# main_board.net
KiCad netlist of a schematic drawn in EAGLE
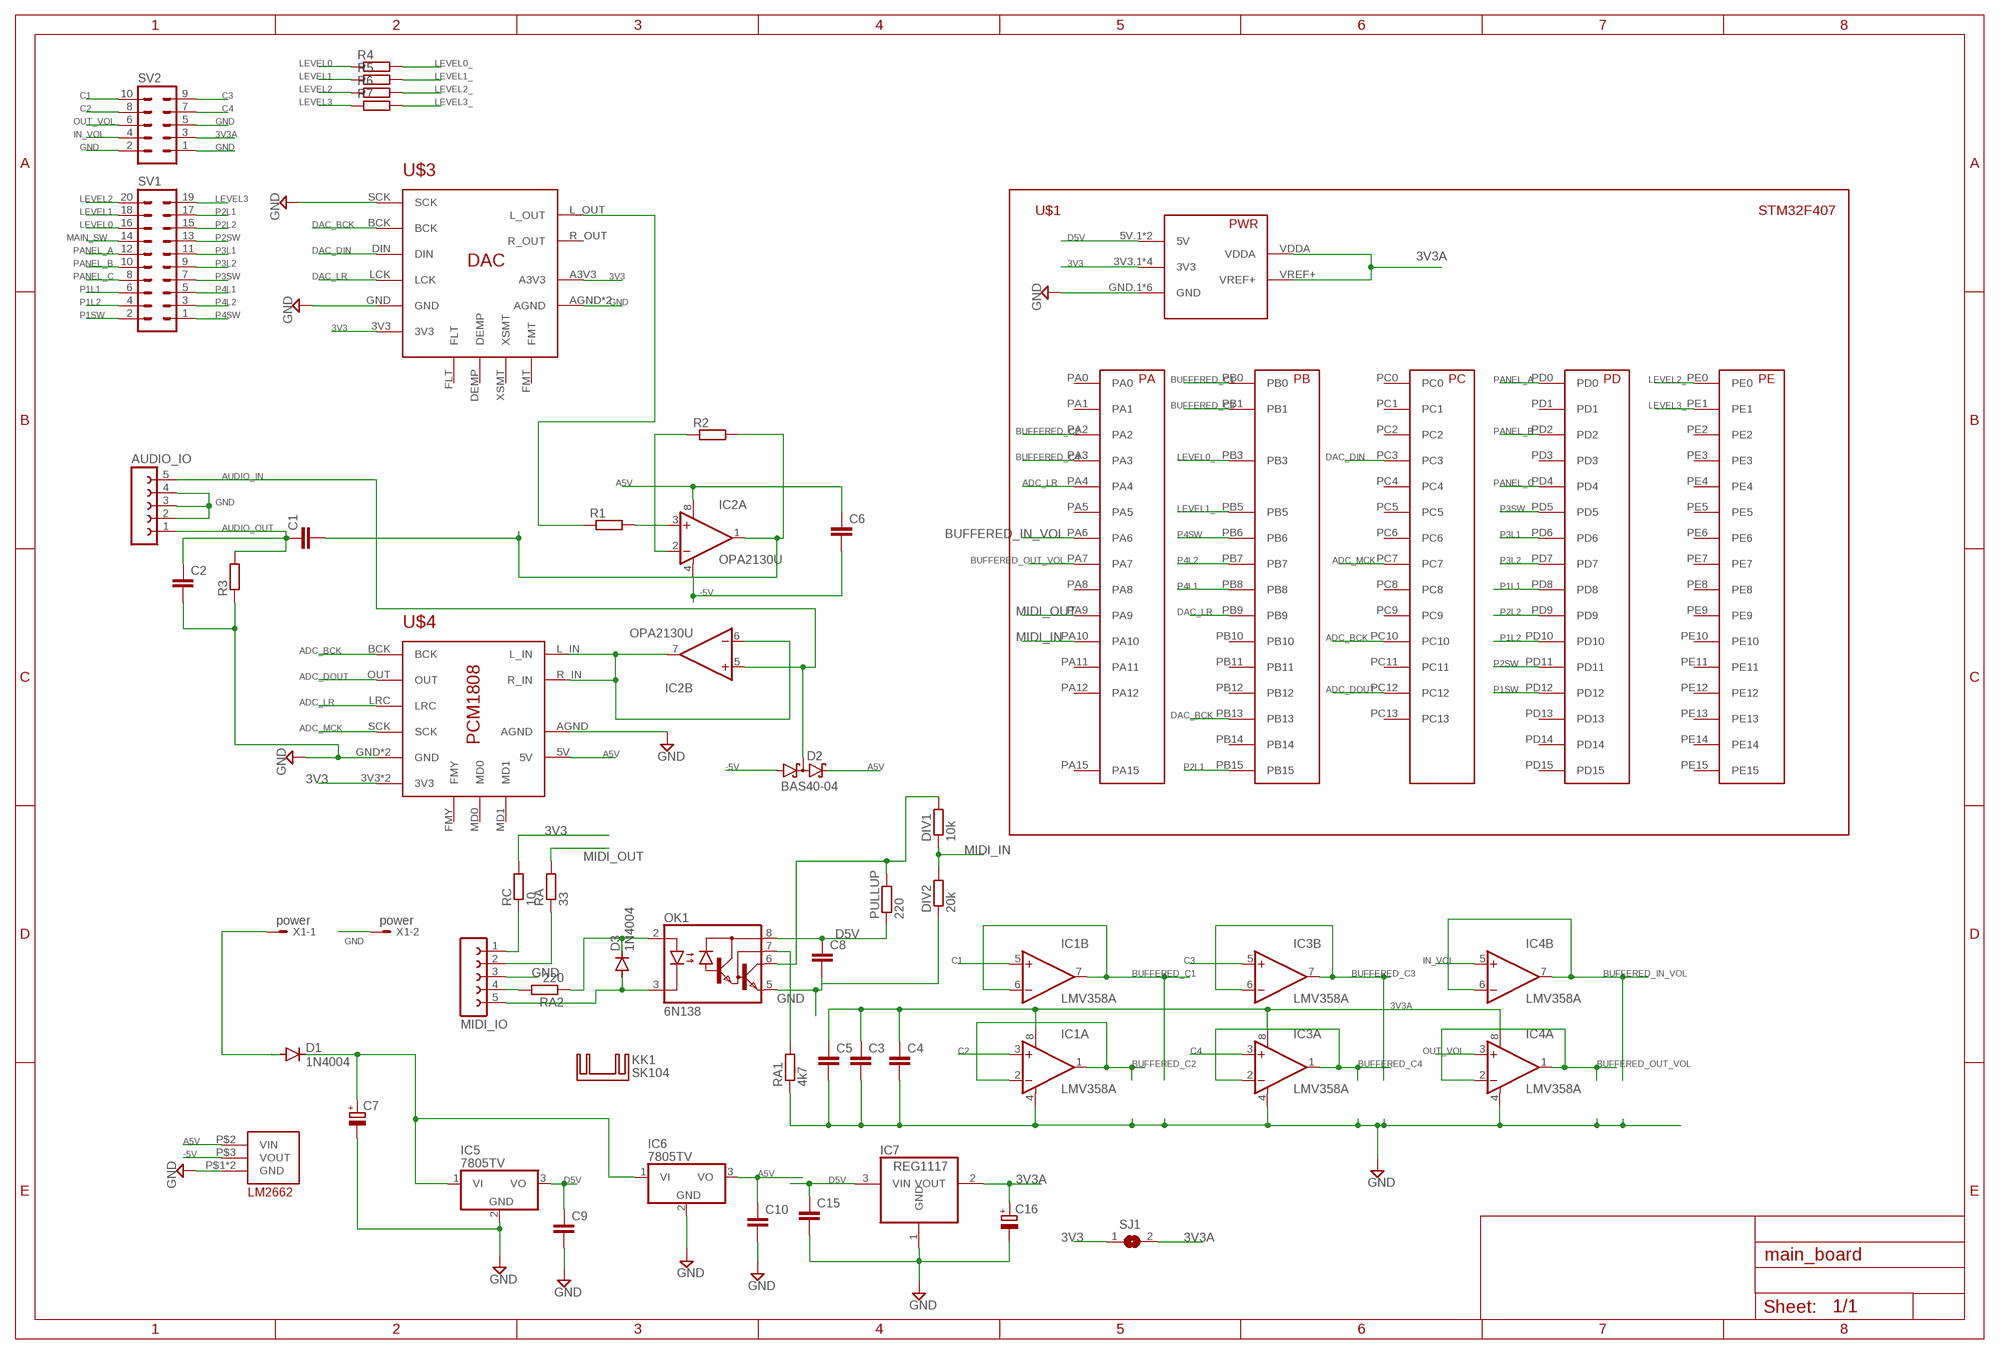
[diagram p0: schematic, sheet 1]

(export (version "E")
  (design (tool "Eeschema 10.0.6"))
  (components
    (comp (ref "AUDIO_IO")
      (value "FE05-1")
      (footprint "eagle-import:FE05-1")
      (libsource (lib "eagle-import") (part "FE05-1"))
    )
    (comp (ref "C1")
      (value "C5/5.5")
      (footprint "eagle-import:C5B5.5")
      (libsource (lib "eagle-import") (part "C5/5.5"))
    )
    (comp (ref "C2")
      (value "C2,5-3")
      (footprint "eagle-import:C2.5-3")
      (libsource (lib "eagle-import") (part "C2,5-3"))
    )
    (comp (ref "C3")
      (value "C-EUC0402")
      (footprint "eagle-import:C0402")
      (libsource (lib "eagle-import") (part "C-EUC0402"))
    )
    (comp (ref "C4")
      (value "C-EUC0402")
      (footprint "eagle-import:C0402")
      (libsource (lib "eagle-import") (part "C-EUC0402"))
    )
    (comp (ref "C5")
      (value "C-EUC0402")
      (footprint "eagle-import:C0402")
      (libsource (lib "eagle-import") (part "C-EUC0402"))
    )
    (comp (ref "C6")
      (value "C-EUC0402")
      (footprint "eagle-import:C0402")
      (libsource (lib "eagle-import") (part "C-EUC0402"))
    )
    (comp (ref "C7")
      (value "CPOL-EUE2.5-7")
      (footprint "eagle-import:E2,5-7")
      (libsource (lib "eagle-import") (part "CPOL-EUE2.5-7"))
    )
    (comp (ref "C8")
      (value "C-EU025-024X044")
      (footprint "eagle-import:C025-024X044")
      (libsource (lib "eagle-import") (part "C-EU025-024X044"))
    )
    (comp (ref "C9")
      (value "C-EU025-024X044")
      (footprint "eagle-import:C025-024X044")
      (libsource (lib "eagle-import") (part "C-EU025-024X044"))
    )
    (comp (ref "C10")
      (value "C-EU025-024X044")
      (footprint "eagle-import:C025-024X044")
      (libsource (lib "eagle-import") (part "C-EU025-024X044"))
    )
    (comp (ref "C15")
      (value "C-EUC0402")
      (footprint "eagle-import:C0402")
      (libsource (lib "eagle-import") (part "C-EUC0402"))
    )
    (comp (ref "C16")
      (value "CPOL-EUTT2D6L")
      (footprint "eagle-import:TT2D6L")
      (libsource (lib "eagle-import") (part "CPOL-EUTT2D6L"))
    )
    (comp (ref "D1")
      (value "1N4004")
      (footprint "eagle-import:DO41-10")
      (libsource (lib "eagle-import") (part "1N4004"))
    )
    (comp (ref "D2")
      (value "BAS40-04")
      (footprint "eagle-import:SOT23")
      (libsource (lib "eagle-import") (part "BAS40-04"))
    )
    (comp (ref "D3")
      (value "1N4004")
      (footprint "eagle-import:DO41-10")
      (libsource (lib "eagle-import") (part "1N4004"))
    )
    (comp (ref "DIV1")
      (value "10k")
      (footprint "eagle-import:0204V")
      (libsource (lib "eagle-import") (part "R-EU_0204/2V"))
    )
    (comp (ref "DIV2")
      (value "20k")
      (footprint "eagle-import:0204V")
      (libsource (lib "eagle-import") (part "R-EU_0204/2V"))
    )
    (comp (ref "IC1")
      (value "LMV358A")
      (footprint "eagle-import:SO08")
      (fields (field (name "MF") "TEXAS INSTRUMENTS") (field (name "MPN") "OPA2130UA"))
      (libsource (lib "eagle-import") (part "OPA2130U"))
    )
    (comp (ref "IC2")
      (value "OPA2130U")
      (footprint "eagle-import:SO08")
      (fields (field (name "MF") "TEXAS INSTRUMENTS") (field (name "MPN") "OPA2130UA"))
      (libsource (lib "eagle-import") (part "OPA2130U"))
    )
    (comp (ref "IC3")
      (value "LMV358A")
      (footprint "eagle-import:SO08")
      (fields (field (name "MF") "TEXAS INSTRUMENTS") (field (name "MPN") "OPA2130UA"))
      (libsource (lib "eagle-import") (part "OPA2130U"))
    )
    (comp (ref "IC4")
      (value "LMV358A")
      (footprint "eagle-import:SO08")
      (fields (field (name "MF") "TEXAS INSTRUMENTS") (field (name "MPN") "OPA2130UA"))
      (libsource (lib "eagle-import") (part "OPA2130U"))
    )
    (comp (ref "IC5")
      (value "7805TV")
      (footprint "eagle-import:TO220V")
      (libsource (lib "eagle-import") (part "78TV05"))
    )
    (comp (ref "IC6")
      (value "7805TV")
      (footprint "eagle-import:TO220V")
      (libsource (lib "eagle-import") (part "78TV05"))
    )
    (comp (ref "IC7")
      (value "REG1117")
      (footprint "eagle-import:SOT223")
      (libsource (lib "eagle-import") (part "REG1117"))
    )
    (comp (ref "KK1")
      (value "SK104")
      (footprint "eagle-import:SK104")
      (libsource (lib "eagle-import") (part "SK104"))
    )
    (comp (ref "MIDI_IO")
      (value "FE05-1")
      (footprint "eagle-import:FE05-1")
      (libsource (lib "eagle-import") (part "FE05-1"))
    )
    (comp (ref "OK1")
      (value "6N138")
      (footprint "eagle-import:DIL08")
      (fields (field (name "MF") "VISHAY/TELEFUNKEN"))
      (libsource (lib "eagle-import") (part "6N138"))
    )
    (comp (ref "PULLUP")
      (value "220")
      (footprint "eagle-import:0204V")
      (libsource (lib "eagle-import") (part "R-EU_0204/2V"))
    )
    (comp (ref "R1")
      (value "R-EU_0204/2V")
      (footprint "eagle-import:0204V")
      (libsource (lib "eagle-import") (part "R-EU_0204/2V"))
    )
    (comp (ref "R2")
      (value "R-EU_0204/2V")
      (footprint "eagle-import:0204V")
      (libsource (lib "eagle-import") (part "R-EU_0204/2V"))
    )
    (comp (ref "R3")
      (value "R-EU_0204/2V")
      (footprint "eagle-import:0204V")
      (libsource (lib "eagle-import") (part "R-EU_0204/2V"))
    )
    (comp (ref "R4")
      (value "R-EU_R0402")
      (footprint "eagle-import:R0402")
      (libsource (lib "eagle-import") (part "R-EU_R0402"))
    )
    (comp (ref "R5")
      (value "R-EU_R0402")
      (footprint "eagle-import:R0402")
      (libsource (lib "eagle-import") (part "R-EU_R0402"))
    )
    (comp (ref "R6")
      (value "R-EU_R0402")
      (footprint "eagle-import:R0402")
      (libsource (lib "eagle-import") (part "R-EU_R0402"))
    )
    (comp (ref "R7")
      (value "R-EU_R0402")
      (footprint "eagle-import:R0402")
      (libsource (lib "eagle-import") (part "R-EU_R0402"))
    )
    (comp (ref "RA")
      (value "33")
      (footprint "eagle-import:0204V")
      (libsource (lib "eagle-import") (part "R-EU_0204/2V"))
    )
    (comp (ref "RA1")
      (value "4k7")
      (footprint "eagle-import:0204V")
      (libsource (lib "eagle-import") (part "R-EU_0204/2V"))
    )
    (comp (ref "RA2")
      (value "220")
      (footprint "eagle-import:0204V")
      (libsource (lib "eagle-import") (part "R-EU_0204/2V"))
    )
    (comp (ref "RC")
      (value "10")
      (footprint "eagle-import:0204V")
      (libsource (lib "eagle-import") (part "R-EU_0204/2V"))
    )
    (comp (ref "SJ1") (value "SJ") (footprint "eagle-import:SJ") (libsource (lib "eagle-import") (part "SJ")))
    (comp (ref "SV1")
      (value "MA10-2")
      (footprint "eagle-import:MA10-2")
      (libsource (lib "eagle-import") (part "MA10-2"))
    )
    (comp (ref "SV2")
      (value "MA05-2")
      (footprint "eagle-import:MA05-2")
      (libsource (lib "eagle-import") (part "MA05-2"))
    )
    (comp (ref "U$1")
      (value "DEVEBOX")
      (footprint "eagle-import:DEVEBOX")
      (libsource (lib "eagle-import") (part "DEVEBOX"))
    )
    (comp (ref "U$2")
      (value "LM2662_MODULE")
      (footprint "eagle-import:LM2662_MODULE")
      (libsource (lib "eagle-import") (part "LM2662_MODULE"))
    )
    (comp (ref "U$3")
      (value "PCM510XA")
      (footprint "eagle-import:DAC_MODULE")
      (libsource (lib "eagle-import") (part "PCM510XA"))
    )
    (comp (ref "U$4")
      (value "PCM1808")
      (footprint "eagle-import:ADC_MODULE")
      (libsource (lib "eagle-import") (part "PCM1808"))
    )
    (comp (ref "X1")
      (value "power")
      (footprint "eagle-import:332-02")
      (libsource (lib "eagle-import") (part "332-02"))
    )
  )
  (nets
    (net (code "1") (name "/-5V") (class "Default")
      (node (ref "C6") (pin "2") (pinfunction "2_2") (pintype "passive"))
      (node (ref "D2") (pin "1") (pinfunction "A1_1") (pintype "passive"))
      (node (ref "IC2") (pin "4") (pinfunction "V-_4") (pintype "power_in"))
      (node (ref "U$2") (pin "P$3") (pinfunction "VOUT_P$3") (pintype "bidirectional"))
    )
    (net (code "2") (name "/3V3") (class "Default")
      (node (ref "RC") (pin "2") (pinfunction "2_2") (pintype "passive"))
      (node (ref "SJ1") (pin "1") (pinfunction "1_1") (pintype "passive"))
      (node (ref "U$1") (pin "3V3.1") (pinfunction "3V3_3V3.1") (pintype "bidirectional"))
      (node (ref "U$1") (pin "3V3.2") (pinfunction "3V3_3V3.2") (pintype "bidirectional"))
      (node (ref "U$1") (pin "3V3.3") (pinfunction "3V3_3V3.3") (pintype "bidirectional"))
      (node (ref "U$1") (pin "3V3.4") (pinfunction "3V3_3V3.4") (pintype "bidirectional"))
      (node (ref "U$3") (pin "3V3") (pinfunction "3V3_3V3") (pintype "bidirectional"))
      (node (ref "U$3") (pin "A3V3") (pinfunction "A3V3_A3V3") (pintype "bidirectional"))
      (node (ref "U$4") (pin "3V3") (pinfunction "3V3_3V3") (pintype "bidirectional"))
      (node (ref "U$4") (pin "3V3.1") (pinfunction "3V3_3V3.1") (pintype "bidirectional"))
    )
    (net (code "3") (name "/3V3A") (class "Default")
      (node (ref "C16") (pin "+") (pinfunction "+_+") (pintype "passive"))
      (node (ref "C3") (pin "1") (pinfunction "1_1") (pintype "passive"))
      (node (ref "C4") (pin "1") (pinfunction "1_1") (pintype "passive"))
      (node (ref "C5") (pin "1") (pinfunction "1_1") (pintype "passive"))
      (node (ref "IC1") (pin "8") (pinfunction "V+_8") (pintype "power_in"))
      (node (ref "IC3") (pin "8") (pinfunction "V+_8") (pintype "power_in"))
      (node (ref "IC4") (pin "8") (pinfunction "V+_8") (pintype "power_in"))
      (node (ref "IC7") (pin "2") (pinfunction "VOUT_2") (pintype "output"))
      (node (ref "SJ1") (pin "2") (pinfunction "2_2") (pintype "passive"))
      (node (ref "SV2") (pin "3") (pinfunction "3_3") (pintype "passive"))
      (node (ref "U$1") (pin "VDDA") (pinfunction "VDDA_VDDA") (pintype "bidirectional"))
      (node (ref "U$1") (pin "VREF+") (pinfunction "VREF+_VREF+") (pintype "bidirectional"))
    )
    (net (code "4") (name "/A5V") (class "Default")
      (node (ref "C10") (pin "1") (pinfunction "1_1") (pintype "passive"))
      (node (ref "C6") (pin "1") (pinfunction "1_1") (pintype "passive"))
      (node (ref "D2") (pin "2") (pinfunction "C2_2") (pintype "passive"))
      (node (ref "IC2") (pin "8") (pinfunction "V+_8") (pintype "power_in"))
      (node (ref "IC6") (pin "3") (pinfunction "VO_3") (pintype "passive"))
      (node (ref "U$2") (pin "P$2") (pinfunction "VIN_P$2") (pintype "bidirectional"))
      (node (ref "U$4") (pin "5V") (pinfunction "5V_5V") (pintype "bidirectional"))
    )
    (net (code "5") (name "/ADC_BCK") (class "Default")
      (node (ref "U$1") (pin "PC10") (pinfunction "PC10_PC10") (pintype "bidirectional"))
      (node (ref "U$4") (pin "BCK") (pinfunction "BCK_BCK") (pintype "bidirectional"))
    )
    (net (code "6") (name "/ADC_DOUT") (class "Default")
      (node (ref "U$1") (pin "PC12") (pinfunction "PC12_PC12") (pintype "bidirectional"))
      (node (ref "U$4") (pin "OUT") (pinfunction "OUT_OUT") (pintype "bidirectional"))
    )
    (net (code "7") (name "/ADC_LR") (class "Default")
      (node (ref "U$1") (pin "PA4") (pinfunction "PA4_PA4") (pintype "bidirectional"))
      (node (ref "U$4") (pin "LRC") (pinfunction "LRC_LRC") (pintype "bidirectional"))
    )
    (net (code "8") (name "/ADC_MCK") (class "Default")
      (node (ref "U$1") (pin "PC7") (pinfunction "PC7_PC7") (pintype "bidirectional"))
      (node (ref "U$4") (pin "SCK") (pinfunction "SCK_SCK") (pintype "bidirectional"))
    )
    (net (code "9") (name "/AUDIO_IN") (class "Default")
      (node (ref "AUDIO_IO") (pin "5") (pinfunction "5_5") (pintype "passive"))
      (node (ref "D2") (pin "3") (pinfunction "C1A2_3") (pintype "passive"))
      (node (ref "IC2") (pin "5") (pinfunction "+IN_5") (pintype "input"))
    )
    (net (code "10") (name "/AUDIO_OUT") (class "Default")
      (node (ref "R1") (pin "1") (pinfunction "1_1") (pintype "passive"))
      (node (ref "U$3") (pin "L_OUT") (pinfunction "L_OUT_L_OUT") (pintype "bidirectional"))
    )
    (net (code "11") (name "/BUFFERED_C1") (class "Default")
      (node (ref "IC1") (pin "6") (pinfunction "-IN_6") (pintype "input"))
      (node (ref "IC1") (pin "7") (pinfunction "OUT_7") (pintype "output"))
      (node (ref "U$1") (pin "PB0") (pinfunction "PB0_PB0") (pintype "bidirectional"))
    )
    (net (code "12") (name "/BUFFERED_C2") (class "Default")
      (node (ref "IC1") (pin "1") (pinfunction "OUT_1") (pintype "output"))
      (node (ref "IC1") (pin "2") (pinfunction "-IN_2") (pintype "input"))
      (node (ref "U$1") (pin "PA2") (pinfunction "PA2_PA2") (pintype "bidirectional"))
    )
    (net (code "13") (name "/BUFFERED_C3") (class "Default")
      (node (ref "IC3") (pin "6") (pinfunction "-IN_6") (pintype "input"))
      (node (ref "IC3") (pin "7") (pinfunction "OUT_7") (pintype "output"))
      (node (ref "U$1") (pin "PB1") (pinfunction "PB1_PB1") (pintype "bidirectional"))
    )
    (net (code "14") (name "/BUFFERED_C4") (class "Default")
      (node (ref "IC3") (pin "1") (pinfunction "OUT_1") (pintype "output"))
      (node (ref "IC3") (pin "2") (pinfunction "-IN_2") (pintype "input"))
      (node (ref "U$1") (pin "PA3") (pinfunction "PA3_PA3") (pintype "bidirectional"))
    )
    (net (code "15") (name "/BUFFERED_IN_VOL") (class "Default")
      (node (ref "IC4") (pin "6") (pinfunction "-IN_6") (pintype "input"))
      (node (ref "IC4") (pin "7") (pinfunction "OUT_7") (pintype "output"))
      (node (ref "U$1") (pin "PA6") (pinfunction "PA6_PA6") (pintype "bidirectional"))
    )
    (net (code "16") (name "/BUFFERED_OUT_VOL") (class "Default")
      (node (ref "IC4") (pin "1") (pinfunction "OUT_1") (pintype "output"))
      (node (ref "IC4") (pin "2") (pinfunction "-IN_2") (pintype "input"))
      (node (ref "U$1") (pin "PA7") (pinfunction "PA7_PA7") (pintype "bidirectional"))
    )
    (net (code "17") (name "/C1") (class "Default")
      (node (ref "IC1") (pin "5") (pinfunction "+IN_5") (pintype "input"))
      (node (ref "SV2") (pin "10") (pinfunction "10_10") (pintype "passive"))
    )
    (net (code "18") (name "/C2") (class "Default")
      (node (ref "IC1") (pin "3") (pinfunction "+IN_3") (pintype "input"))
      (node (ref "SV2") (pin "8") (pinfunction "8_8") (pintype "passive"))
    )
    (net (code "19") (name "/C3") (class "Default")
      (node (ref "IC3") (pin "5") (pinfunction "+IN_5") (pintype "input"))
      (node (ref "SV2") (pin "9") (pinfunction "9_9") (pintype "passive"))
    )
    (net (code "20") (name "/C4") (class "Default")
      (node (ref "IC3") (pin "3") (pinfunction "+IN_3") (pintype "input"))
      (node (ref "SV2") (pin "7") (pinfunction "7_7") (pintype "passive"))
    )
    (net (code "21") (name "/D5V") (class "Default")
      (node (ref "C15") (pin "1") (pinfunction "1_1") (pintype "passive"))
      (node (ref "C8") (pin "1") (pinfunction "1_1") (pintype "passive"))
      (node (ref "C9") (pin "1") (pinfunction "1_1") (pintype "passive"))
      (node (ref "IC5") (pin "3") (pinfunction "VO_3") (pintype "passive"))
      (node (ref "IC7") (pin "3") (pinfunction "VIN_3") (pintype "input"))
      (node (ref "OK1") (pin "8") (pinfunction "VCC_8") (pintype "passive"))
      (node (ref "PULLUP") (pin "1") (pinfunction "1_1") (pintype "passive"))
      (node (ref "U$1") (pin "5V.1") (pinfunction "5V_5V.1") (pintype "bidirectional"))
      (node (ref "U$1") (pin "5V.2") (pinfunction "5V_5V.2") (pintype "bidirectional"))
    )
    (net (code "22") (name "/DAC_BCK") (class "Default")
      (node (ref "U$1") (pin "PB13") (pinfunction "PB13_PB13") (pintype "bidirectional"))
      (node (ref "U$3") (pin "BCK") (pinfunction "BCK_BCK") (pintype "bidirectional"))
    )
    (net (code "23") (name "/DAC_DIN") (class "Default")
      (node (ref "U$1") (pin "PC3") (pinfunction "PC3_PC3") (pintype "bidirectional"))
      (node (ref "U$3") (pin "DIN") (pinfunction "DIN_DIN") (pintype "bidirectional"))
    )
    (net (code "24") (name "/DAC_LR") (class "Default")
      (node (ref "U$1") (pin "PB9") (pinfunction "PB9_PB9") (pintype "bidirectional"))
      (node (ref "U$3") (pin "LCK") (pinfunction "LCK_LCK") (pintype "bidirectional"))
    )
    (net (code "25") (name "/IN_VOL") (class "Default")
      (node (ref "IC4") (pin "5") (pinfunction "+IN_5") (pintype "input"))
      (node (ref "SV2") (pin "4") (pinfunction "4_4") (pintype "passive"))
    )
    (net (code "26") (name "/LEVEL0") (class "Default")
      (node (ref "R4") (pin "1") (pinfunction "1_1") (pintype "passive"))
      (node (ref "SV1") (pin "16") (pinfunction "16_16") (pintype "passive"))
    )
    (net (code "27") (name "/LEVEL0_") (class "Default")
      (node (ref "R4") (pin "2") (pinfunction "2_2") (pintype "passive"))
      (node (ref "U$1") (pin "PB3") (pinfunction "PB3_PB3") (pintype "bidirectional"))
    )
    (net (code "28") (name "/LEVEL1") (class "Default")
      (node (ref "R5") (pin "1") (pinfunction "1_1") (pintype "passive"))
      (node (ref "SV1") (pin "18") (pinfunction "18_18") (pintype "passive"))
    )
    (net (code "29") (name "/LEVEL1_") (class "Default")
      (node (ref "R5") (pin "2") (pinfunction "2_2") (pintype "passive"))
      (node (ref "U$1") (pin "PB5") (pinfunction "PB5_PB5") (pintype "bidirectional"))
    )
    (net (code "30") (name "/LEVEL2") (class "Default")
      (node (ref "R6") (pin "1") (pinfunction "1_1") (pintype "passive"))
      (node (ref "SV1") (pin "20") (pinfunction "20_20") (pintype "passive"))
    )
    (net (code "31") (name "/LEVEL2_") (class "Default")
      (node (ref "R6") (pin "2") (pinfunction "2_2") (pintype "passive"))
      (node (ref "U$1") (pin "PE0") (pinfunction "PE0_PE0") (pintype "bidirectional"))
    )
    (net (code "32") (name "/LEVEL3") (class "Default")
      (node (ref "R7") (pin "1") (pinfunction "1_1") (pintype "passive"))
      (node (ref "SV1") (pin "19") (pinfunction "19_19") (pintype "passive"))
    )
    (net (code "33") (name "/LEVEL3_") (class "Default")
      (node (ref "R7") (pin "2") (pinfunction "2_2") (pintype "passive"))
      (node (ref "U$1") (pin "PE1") (pinfunction "PE1_PE1") (pintype "bidirectional"))
    )
    (net (code "34") (name "/MAIN_SW") (class "Default")
      (node (ref "SV1") (pin "14") (pinfunction "14_14") (pintype "passive"))
    )
    (net (code "35") (name "/MIDI_IN") (class "Default")
      (node (ref "DIV1") (pin "1") (pinfunction "1_1") (pintype "passive"))
      (node (ref "DIV2") (pin "2") (pinfunction "2_2") (pintype "passive"))
      (node (ref "U$1") (pin "PA10") (pinfunction "PA10_PA10") (pintype "bidirectional"))
    )
    (net (code "36") (name "/MIDI_OUT") (class "Default")
      (node (ref "RA") (pin "2") (pinfunction "2_2") (pintype "passive"))
      (node (ref "U$1") (pin "PA9") (pinfunction "PA9_PA9") (pintype "bidirectional"))
    )
    (net (code "37") (name "/OUT_VOL") (class "Default")
      (node (ref "IC4") (pin "3") (pinfunction "+IN_3") (pintype "input"))
      (node (ref "SV2") (pin "6") (pinfunction "6_6") (pintype "passive"))
    )
    (net (code "38") (name "/P1L1") (class "Default")
      (node (ref "SV1") (pin "6") (pinfunction "6_6") (pintype "passive"))
      (node (ref "U$1") (pin "PD8") (pinfunction "PD8_PD8") (pintype "bidirectional"))
    )
    (net (code "39") (name "/P1L2") (class "Default")
      (node (ref "SV1") (pin "4") (pinfunction "4_4") (pintype "passive"))
      (node (ref "U$1") (pin "PD10") (pinfunction "PD10_PD10") (pintype "bidirectional"))
    )
    (net (code "40") (name "/P1SW") (class "Default")
      (node (ref "SV1") (pin "2") (pinfunction "2_2") (pintype "passive"))
      (node (ref "U$1") (pin "PD12") (pinfunction "PD12_PD12") (pintype "bidirectional"))
    )
    (net (code "41") (name "/P2L1") (class "Default")
      (node (ref "SV1") (pin "17") (pinfunction "17_17") (pintype "passive"))
      (node (ref "U$1") (pin "PB15") (pinfunction "PB15_PB15") (pintype "bidirectional"))
    )
    (net (code "42") (name "/P2L2") (class "Default")
      (node (ref "SV1") (pin "15") (pinfunction "15_15") (pintype "passive"))
      (node (ref "U$1") (pin "PD9") (pinfunction "PD9_PD9") (pintype "bidirectional"))
    )
    (net (code "43") (name "/P2SW") (class "Default")
      (node (ref "SV1") (pin "13") (pinfunction "13_13") (pintype "passive"))
      (node (ref "U$1") (pin "PD11") (pinfunction "PD11_PD11") (pintype "bidirectional"))
    )
    (net (code "44") (name "/P3L1") (class "Default")
      (node (ref "SV1") (pin "11") (pinfunction "11_11") (pintype "passive"))
      (node (ref "U$1") (pin "PD6") (pinfunction "PD6_PD6") (pintype "bidirectional"))
    )
    (net (code "45") (name "/P3L2") (class "Default")
      (node (ref "SV1") (pin "9") (pinfunction "9_9") (pintype "passive"))
      (node (ref "U$1") (pin "PD7") (pinfunction "PD7_PD7") (pintype "bidirectional"))
    )
    (net (code "46") (name "/P3SW") (class "Default")
      (node (ref "SV1") (pin "7") (pinfunction "7_7") (pintype "passive"))
      (node (ref "U$1") (pin "PD5") (pinfunction "PD5_PD5") (pintype "bidirectional"))
    )
    (net (code "47") (name "/P4L1") (class "Default")
      (node (ref "SV1") (pin "5") (pinfunction "5_5") (pintype "passive"))
      (node (ref "U$1") (pin "PB8") (pinfunction "PB8_PB8") (pintype "bidirectional"))
    )
    (net (code "48") (name "/P4L2") (class "Default")
      (node (ref "SV1") (pin "3") (pinfunction "3_3") (pintype "passive"))
      (node (ref "U$1") (pin "PB7") (pinfunction "PB7_PB7") (pintype "bidirectional"))
    )
    (net (code "49") (name "/P4SW") (class "Default")
      (node (ref "SV1") (pin "1") (pinfunction "1_1") (pintype "passive"))
      (node (ref "U$1") (pin "PB6") (pinfunction "PB6_PB6") (pintype "bidirectional"))
    )
    (net (code "50") (name "/PANEL_A") (class "Default")
      (node (ref "SV1") (pin "12") (pinfunction "12_12") (pintype "passive"))
      (node (ref "U$1") (pin "PD0") (pinfunction "PD0_PD0") (pintype "bidirectional"))
    )
    (net (code "51") (name "/PANEL_B") (class "Default")
      (node (ref "SV1") (pin "10") (pinfunction "10_10") (pintype "passive"))
      (node (ref "U$1") (pin "PD2") (pinfunction "PD2_PD2") (pintype "bidirectional"))
    )
    (net (code "52") (name "/PANEL_C") (class "Default")
      (node (ref "SV1") (pin "8") (pinfunction "8_8") (pintype "passive"))
      (node (ref "U$1") (pin "PD4") (pinfunction "PD4_PD4") (pintype "bidirectional"))
    )
    (net (code "53") (name "GND") (class "Default")
      (node (ref "AUDIO_IO") (pin "2") (pinfunction "2_2") (pintype "passive"))
      (node (ref "AUDIO_IO") (pin "3") (pinfunction "3_3") (pintype "passive"))
      (node (ref "AUDIO_IO") (pin "4") (pinfunction "4_4") (pintype "passive"))
      (node (ref "C10") (pin "2") (pinfunction "2_2") (pintype "passive"))
      (node (ref "C15") (pin "2") (pinfunction "2_2") (pintype "passive"))
      (node (ref "C16") (pin "-") (pinfunction "-_-") (pintype "passive"))
      (node (ref "C2") (pin "2") (pinfunction "2_2") (pintype "passive"))
      (node (ref "C3") (pin "2") (pinfunction "2_2") (pintype "passive"))
      (node (ref "C4") (pin "2") (pinfunction "2_2") (pintype "passive"))
      (node (ref "C5") (pin "2") (pinfunction "2_2") (pintype "passive"))
      (node (ref "C7") (pin "-") (pinfunction "-_-") (pintype "passive"))
      (node (ref "C8") (pin "2") (pinfunction "2_2") (pintype "passive"))
      (node (ref "C9") (pin "2") (pinfunction "2_2") (pintype "passive"))
      (node (ref "DIV2") (pin "1") (pinfunction "1_1") (pintype "passive"))
      (node (ref "IC1") (pin "4") (pinfunction "V-_4") (pintype "power_in"))
      (node (ref "IC3") (pin "4") (pinfunction "V-_4") (pintype "power_in"))
      (node (ref "IC4") (pin "4") (pinfunction "V-_4") (pintype "power_in"))
      (node (ref "IC5") (pin "2") (pinfunction "GND_2") (pintype "passive"))
      (node (ref "IC6") (pin "2") (pinfunction "GND_2") (pintype "passive"))
      (node (ref "IC7") (pin "1") (pinfunction "GND_1") (pintype "power_in"))
      (node (ref "MIDI_IO") (pin "3") (pinfunction "3_3") (pintype "passive"))
      (node (ref "OK1") (pin "5") (pinfunction "GND_5") (pintype "passive"))
      (node (ref "R3") (pin "1") (pinfunction "1_1") (pintype "passive"))
      (node (ref "RA1") (pin "1") (pinfunction "1_1") (pintype "passive"))
      (node (ref "SV2") (pin "1") (pinfunction "1_1") (pintype "passive"))
      (node (ref "SV2") (pin "2") (pinfunction "2_2") (pintype "passive"))
      (node (ref "SV2") (pin "5") (pinfunction "5_5") (pintype "passive"))
      (node (ref "U$1") (pin "GND.1") (pinfunction "GND_GND.1") (pintype "bidirectional"))
      (node (ref "U$1") (pin "GND.2") (pinfunction "GND_GND.2") (pintype "bidirectional"))
      (node (ref "U$1") (pin "GND.3") (pinfunction "GND_GND.3") (pintype "bidirectional"))
      (node (ref "U$1") (pin "GND.6") (pinfunction "GND_GND.6") (pintype "bidirectional"))
      (node (ref "U$1") (pin "GND.7") (pinfunction "GND_GND.7") (pintype "bidirectional"))
      (node (ref "U$1") (pin "GND4.") (pinfunction "GND_GND4.") (pintype "bidirectional"))
      (node (ref "U$2") (pin "P$1") (pinfunction "GND_P$1") (pintype "bidirectional"))
      (node (ref "U$2") (pin "P$4") (pinfunction "GND_P$4") (pintype "bidirectional"))
      (node (ref "U$3") (pin "AGND") (pinfunction "AGND_AGND") (pintype "bidirectional"))
      (node (ref "U$3") (pin "AGND.1") (pinfunction "AGND_AGND.1") (pintype "bidirectional"))
      (node (ref "U$3") (pin "GND") (pinfunction "GND_GND") (pintype "bidirectional"))
      (node (ref "U$3") (pin "SCK") (pinfunction "SCK_SCK") (pintype "bidirectional"))
      (node (ref "U$4") (pin "AGND") (pinfunction "AGND_AGND") (pintype "bidirectional"))
      (node (ref "U$4") (pin "GND") (pinfunction "GND_GND") (pintype "bidirectional"))
      (node (ref "U$4") (pin "GND.1") (pinfunction "GND_GND.1") (pintype "bidirectional"))
      (node (ref "X1") (pin "2") (pinfunction "S_2") (pintype "passive"))
    )
    (net (code "54") (name "Net-(AUDIO_IO-Pad1)") (class "Default")
      (node (ref "AUDIO_IO") (pin "1") (pinfunction "1_1") (pintype "passive"))
      (node (ref "C1") (pin "1") (pinfunction "1_1") (pintype "passive"))
      (node (ref "C2") (pin "1") (pinfunction "1_1") (pintype "passive"))
      (node (ref "R3") (pin "2") (pinfunction "2_2") (pintype "passive"))
    )
    (net (code "55") (name "Net-(IC2A-+IN)") (class "Default")
      (node (ref "IC2") (pin "3") (pinfunction "+IN_3") (pintype "input"))
      (node (ref "R1") (pin "2") (pinfunction "2_2") (pintype "passive"))
    )
    (net (code "56") (name "Net-(IC2A--IN)") (class "Default")
      (node (ref "IC2") (pin "2") (pinfunction "-IN_2") (pintype "input"))
      (node (ref "R2") (pin "1") (pinfunction "1_1") (pintype "passive"))
    )
    (net (code "57") (name "Net-(IC2A-OUT)") (class "Default")
      (node (ref "C1") (pin "2") (pinfunction "2_2") (pintype "passive"))
      (node (ref "IC2") (pin "1") (pinfunction "OUT_1") (pintype "output"))
      (node (ref "R2") (pin "2") (pinfunction "2_2") (pintype "passive"))
    )
    (net (code "58") (name "Net-(IC2B--IN)") (class "Default")
      (node (ref "IC2") (pin "6") (pinfunction "-IN_6") (pintype "input"))
      (node (ref "IC2") (pin "7") (pinfunction "OUT_7") (pintype "output"))
      (node (ref "U$4") (pin "L_IN") (pinfunction "L_IN_L_IN") (pintype "bidirectional"))
      (node (ref "U$4") (pin "R_IN") (pinfunction "R_IN_R_IN") (pintype "bidirectional"))
    )
    (net (code "59") (name "Net-(IC5-VI)") (class "Default")
      (node (ref "C7") (pin "+") (pinfunction "+_+") (pintype "passive"))
      (node (ref "D1") (pin "C") (pinfunction "C_C") (pintype "passive"))
      (node (ref "IC5") (pin "1") (pinfunction "VI_1") (pintype "input"))
      (node (ref "IC6") (pin "1") (pinfunction "VI_1") (pintype "input"))
    )
    (net (code "60") (name "Net-(MIDI_IO-Pad1)") (class "Default")
      (node (ref "MIDI_IO") (pin "1") (pinfunction "1_1") (pintype "passive"))
      (node (ref "RC") (pin "1") (pinfunction "1_1") (pintype "passive"))
    )
    (net (code "61") (name "Net-(MIDI_IO-Pad2)") (class "Default")
      (node (ref "MIDI_IO") (pin "2") (pinfunction "2_2") (pintype "passive"))
      (node (ref "RA") (pin "1") (pinfunction "1_1") (pintype "passive"))
    )
    (net (code "62") (name "Net-(MIDI_IO-Pad4)") (class "Default")
      (node (ref "MIDI_IO") (pin "4") (pinfunction "4_4") (pintype "passive"))
      (node (ref "RA2") (pin "2") (pinfunction "2_2") (pintype "passive"))
    )
    (net (code "63") (name "Net-(OK1-A)") (class "Default")
      (node (ref "D3") (pin "C") (pinfunction "C_C") (pintype "passive"))
      (node (ref "OK1") (pin "2") (pinfunction "A_2") (pintype "passive"))
      (node (ref "RA2") (pin "1") (pinfunction "1_1") (pintype "passive"))
    )
    (net (code "64") (name "Net-(OK1-C)") (class "Default")
      (node (ref "D3") (pin "A") (pinfunction "A_A") (pintype "passive"))
      (node (ref "MIDI_IO") (pin "5") (pinfunction "5_5") (pintype "passive"))
      (node (ref "OK1") (pin "3") (pinfunction "C_3") (pintype "passive"))
    )
    (net (code "65") (name "Net-(OK1-VB)") (class "Default")
      (node (ref "OK1") (pin "7") (pinfunction "VB_7") (pintype "passive"))
      (node (ref "RA1") (pin "2") (pinfunction "2_2") (pintype "passive"))
    )
    (net (code "66") (name "Net-(OK1-VO)") (class "Default")
      (node (ref "DIV1") (pin "2") (pinfunction "2_2") (pintype "passive"))
      (node (ref "OK1") (pin "6") (pinfunction "VO_6") (pintype "passive"))
      (node (ref "PULLUP") (pin "2") (pinfunction "2_2") (pintype "passive"))
    )
    (net (code "67") (name "Net-(X1A-S)") (class "Default")
      (node (ref "D1") (pin "A") (pinfunction "A_A") (pintype "passive"))
      (node (ref "X1") (pin "1") (pinfunction "S_1") (pintype "passive"))
    )
    (net (code "68") (name "unconnected-(U$1-PadPA0)") (class "Default")
      (node (ref "U$1") (pin "PA0") (pinfunction "PA0_PA0") (pintype "bidirectional"))
    )
    (net (code "69") (name "unconnected-(U$1-PadPA1)") (class "Default")
      (node (ref "U$1") (pin "PA1") (pinfunction "PA1_PA1") (pintype "bidirectional"))
    )
    (net (code "70") (name "unconnected-(U$1-PadPA5)") (class "Default")
      (node (ref "U$1") (pin "PA5") (pinfunction "PA5_PA5") (pintype "bidirectional"))
    )
    (net (code "71") (name "unconnected-(U$1-PadPA8)") (class "Default")
      (node (ref "U$1") (pin "PA8") (pinfunction "PA8_PA8") (pintype "bidirectional"))
    )
    (net (code "72") (name "unconnected-(U$1-PadPA11)") (class "Default")
      (node (ref "U$1") (pin "PA11") (pinfunction "PA11_PA11") (pintype "bidirectional"))
    )
    (net (code "73") (name "unconnected-(U$1-PadPA12)") (class "Default")
      (node (ref "U$1") (pin "PA12") (pinfunction "PA12_PA12") (pintype "bidirectional"))
    )
    (net (code "74") (name "unconnected-(U$1-PadPA15)") (class "Default")
      (node (ref "U$1") (pin "PA15") (pinfunction "PA15_PA15") (pintype "bidirectional"))
    )
    (net (code "75") (name "unconnected-(U$1-PadPB10)") (class "Default")
      (node (ref "U$1") (pin "PB10") (pinfunction "PB10_PB10") (pintype "bidirectional"))
    )
    (net (code "76") (name "unconnected-(U$1-PadPB11)") (class "Default")
      (node (ref "U$1") (pin "PB11") (pinfunction "PB11_PB11") (pintype "bidirectional"))
    )
    (net (code "77") (name "unconnected-(U$1-PadPB12)") (class "Default")
      (node (ref "U$1") (pin "PB12") (pinfunction "PB12_PB12") (pintype "bidirectional"))
    )
    (net (code "78") (name "unconnected-(U$1-PadPB14)") (class "Default")
      (node (ref "U$1") (pin "PB14") (pinfunction "PB14_PB14") (pintype "bidirectional"))
    )
    (net (code "79") (name "unconnected-(U$1-PadPC0)") (class "Default")
      (node (ref "U$1") (pin "PC0") (pinfunction "PC0_PC0") (pintype "bidirectional"))
    )
    (net (code "80") (name "unconnected-(U$1-PadPC1)") (class "Default")
      (node (ref "U$1") (pin "PC1") (pinfunction "PC1_PC1") (pintype "bidirectional"))
    )
    (net (code "81") (name "unconnected-(U$1-PadPC2)") (class "Default")
      (node (ref "U$1") (pin "PC2") (pinfunction "PC2_PC2") (pintype "bidirectional"))
    )
    (net (code "82") (name "unconnected-(U$1-PadPC4)") (class "Default")
      (node (ref "U$1") (pin "PC4") (pinfunction "PC4_PC4") (pintype "bidirectional"))
    )
    (net (code "83") (name "unconnected-(U$1-PadPC5)") (class "Default")
      (node (ref "U$1") (pin "PC5") (pinfunction "PC5_PC5") (pintype "bidirectional"))
    )
    (net (code "84") (name "unconnected-(U$1-PadPC6)") (class "Default")
      (node (ref "U$1") (pin "PC6") (pinfunction "PC6_PC6") (pintype "bidirectional"))
    )
    (net (code "85") (name "unconnected-(U$1-PadPC8)") (class "Default")
      (node (ref "U$1") (pin "PC8") (pinfunction "PC8_PC8") (pintype "bidirectional"))
    )
    (net (code "86") (name "unconnected-(U$1-PadPC9)") (class "Default")
      (node (ref "U$1") (pin "PC9") (pinfunction "PC9_PC9") (pintype "bidirectional"))
    )
    (net (code "87") (name "unconnected-(U$1-PadPC11)") (class "Default")
      (node (ref "U$1") (pin "PC11") (pinfunction "PC11_PC11") (pintype "bidirectional"))
    )
    (net (code "88") (name "unconnected-(U$1-PadPC13)") (class "Default")
      (node (ref "U$1") (pin "PC13") (pinfunction "PC13_PC13") (pintype "bidirectional"))
    )
    (net (code "89") (name "unconnected-(U$1-PadPD1)") (class "Default")
      (node (ref "U$1") (pin "PD1") (pinfunction "PD1_PD1") (pintype "bidirectional"))
    )
    (net (code "90") (name "unconnected-(U$1-PadPD3)") (class "Default")
      (node (ref "U$1") (pin "PD3") (pinfunction "PD3_PD3") (pintype "bidirectional"))
    )
    (net (code "91") (name "unconnected-(U$1-PadPD13)") (class "Default")
      (node (ref "U$1") (pin "PD13") (pinfunction "PD13_PD13") (pintype "bidirectional"))
    )
    (net (code "92") (name "unconnected-(U$1-PadPD14)") (class "Default")
      (node (ref "U$1") (pin "PD14") (pinfunction "PD14_PD14") (pintype "bidirectional"))
    )
    (net (code "93") (name "unconnected-(U$1-PadPD15)") (class "Default")
      (node (ref "U$1") (pin "PD15") (pinfunction "PD15_PD15") (pintype "bidirectional"))
    )
    (net (code "94") (name "unconnected-(U$1-PadPE2)") (class "Default")
      (node (ref "U$1") (pin "PE2") (pinfunction "PE2_PE2") (pintype "bidirectional"))
    )
    (net (code "95") (name "unconnected-(U$1-PadPE3)") (class "Default")
      (node (ref "U$1") (pin "PE3") (pinfunction "PE3_PE3") (pintype "bidirectional"))
    )
    (net (code "96") (name "unconnected-(U$1-PadPE4)") (class "Default")
      (node (ref "U$1") (pin "PE4") (pinfunction "PE4_PE4") (pintype "bidirectional"))
    )
    (net (code "97") (name "unconnected-(U$1-PadPE5)") (class "Default")
      (node (ref "U$1") (pin "PE5") (pinfunction "PE5_PE5") (pintype "bidirectional"))
    )
    (net (code "98") (name "unconnected-(U$1-PadPE6)") (class "Default")
      (node (ref "U$1") (pin "PE6") (pinfunction "PE6_PE6") (pintype "bidirectional"))
    )
    (net (code "99") (name "unconnected-(U$1-PadPE7)") (class "Default")
      (node (ref "U$1") (pin "PE7") (pinfunction "PE7_PE7") (pintype "bidirectional"))
    )
    (net (code "100") (name "unconnected-(U$1-PadPE8)") (class "Default")
      (node (ref "U$1") (pin "PE8") (pinfunction "PE8_PE8") (pintype "bidirectional"))
    )
    (net (code "101") (name "unconnected-(U$1-PadPE9)") (class "Default")
      (node (ref "U$1") (pin "PE9") (pinfunction "PE9_PE9") (pintype "bidirectional"))
    )
    (net (code "102") (name "unconnected-(U$1-PadPE10)") (class "Default")
      (node (ref "U$1") (pin "PE10") (pinfunction "PE10_PE10") (pintype "bidirectional"))
    )
    (net (code "103") (name "unconnected-(U$1-PadPE11)") (class "Default")
      (node (ref "U$1") (pin "PE11") (pinfunction "PE11_PE11") (pintype "bidirectional"))
    )
    (net (code "104") (name "unconnected-(U$1-PadPE12)") (class "Default")
      (node (ref "U$1") (pin "PE12") (pinfunction "PE12_PE12") (pintype "bidirectional"))
    )
    (net (code "105") (name "unconnected-(U$1-PadPE13)") (class "Default")
      (node (ref "U$1") (pin "PE13") (pinfunction "PE13_PE13") (pintype "bidirectional"))
    )
    (net (code "106") (name "unconnected-(U$1-PadPE14)") (class "Default")
      (node (ref "U$1") (pin "PE14") (pinfunction "PE14_PE14") (pintype "bidirectional"))
    )
    (net (code "107") (name "unconnected-(U$1-PadPE15)") (class "Default")
      (node (ref "U$1") (pin "PE15") (pinfunction "PE15_PE15") (pintype "bidirectional"))
    )
    (net (code "108") (name "unconnected-(U$3-PadDEMP)") (class "Default")
      (node (ref "U$3") (pin "DEMP") (pinfunction "DEMP_DEMP") (pintype "bidirectional"))
    )
    (net (code "109") (name "unconnected-(U$3-PadFLT)") (class "Default")
      (node (ref "U$3") (pin "FLT") (pinfunction "FLT_FLT") (pintype "bidirectional"))
    )
    (net (code "110") (name "unconnected-(U$3-PadFMT)") (class "Default")
      (node (ref "U$3") (pin "FMT") (pinfunction "FMT_FMT") (pintype "bidirectional"))
    )
    (net (code "111") (name "unconnected-(U$3-PadR_OUT)") (class "Default")
      (node (ref "U$3") (pin "R_OUT") (pinfunction "R_OUT_R_OUT") (pintype "bidirectional"))
    )
    (net (code "112") (name "unconnected-(U$3-PadXSMT)") (class "Default")
      (node (ref "U$3") (pin "XSMT") (pinfunction "XSMT_XSMT") (pintype "bidirectional"))
    )
    (net (code "113") (name "unconnected-(U$4-PadFMY)") (class "Default")
      (node (ref "U$4") (pin "FMY") (pinfunction "FMY_FMY") (pintype "bidirectional"))
    )
    (net (code "114") (name "unconnected-(U$4-PadMD0)") (class "Default")
      (node (ref "U$4") (pin "MD0") (pinfunction "MD0_MD0") (pintype "bidirectional"))
    )
    (net (code "115") (name "unconnected-(U$4-PadMD1)") (class "Default")
      (node (ref "U$4") (pin "MD1") (pinfunction "MD1_MD1") (pintype "bidirectional"))
    )
  )
)
